# ME433_PCB_Schematic.net
KiCad netlist of a schematic drawn in EAGLE
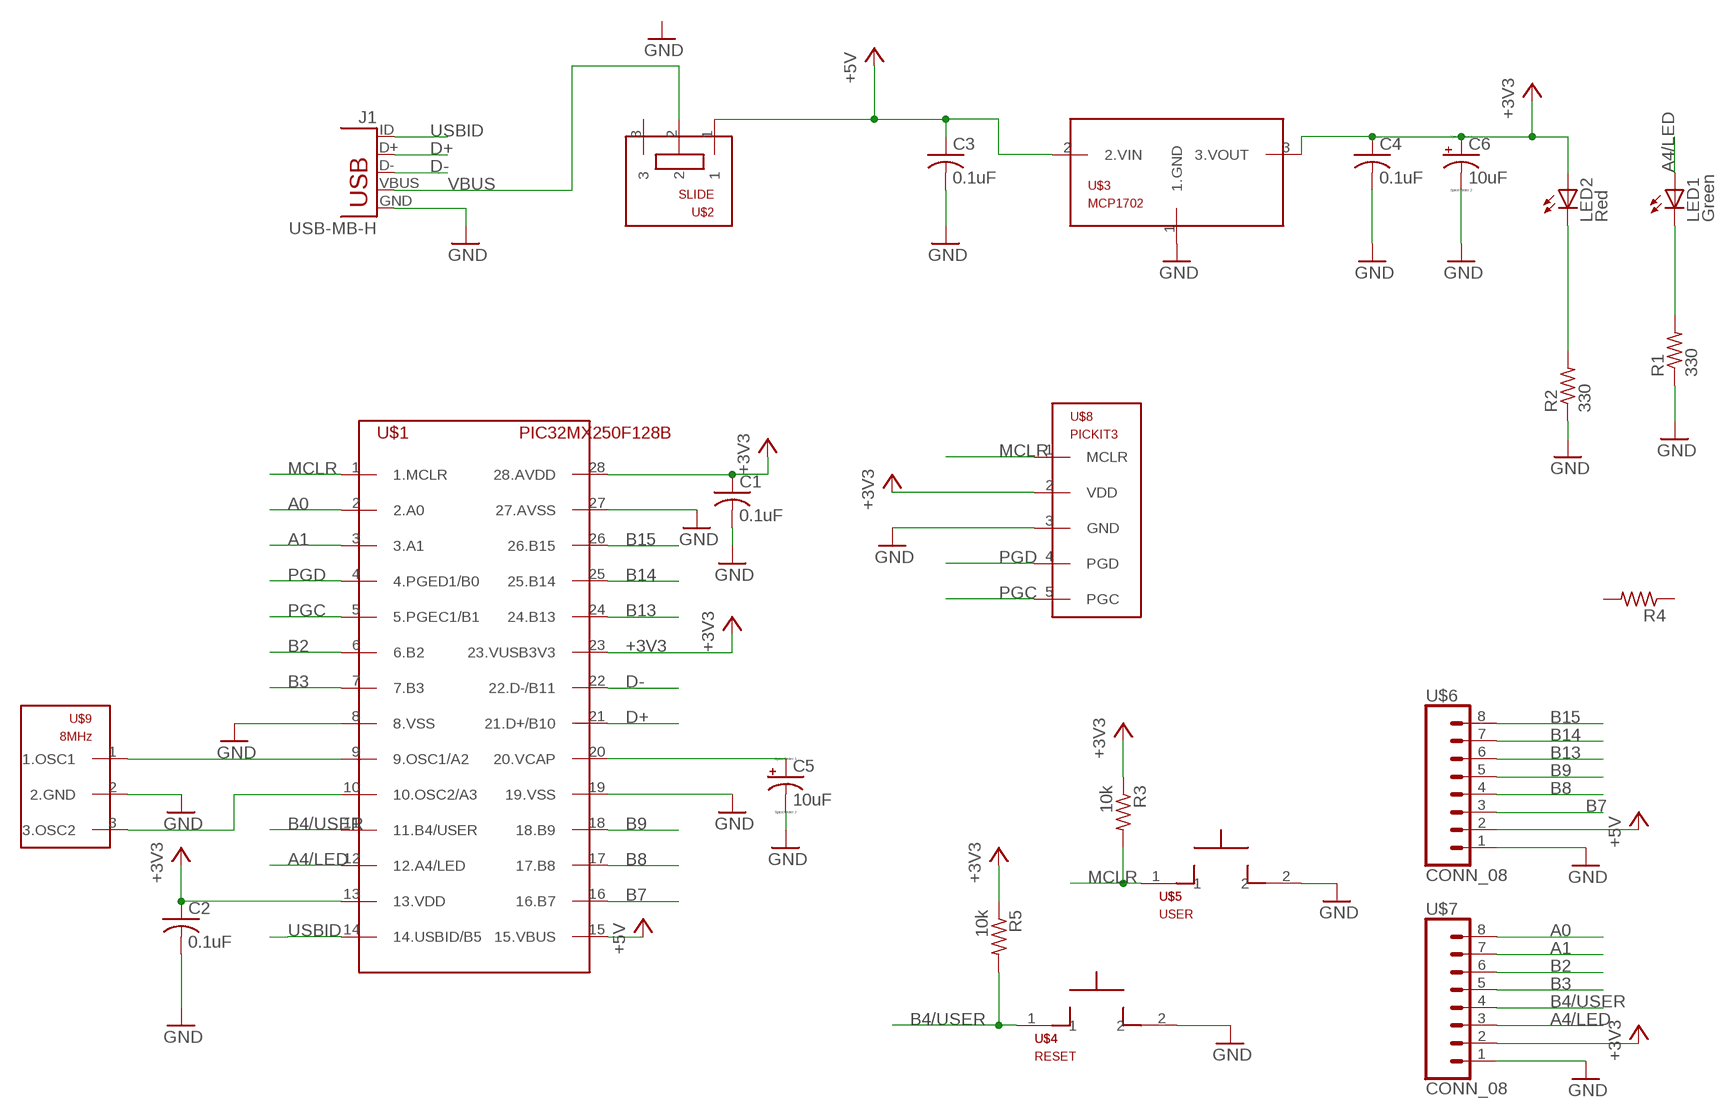
[diagram p0: schematic, sheet 1]

(export (version "E")
  (design (tool "Eeschema 10.0.6"))
  (components
    (comp (ref "C1")
      (value "0.1uF")
      (footprint "eagle-import:C025-025X050")
      (libsource (lib "eagle-import") (part "C-US025-025X050"))
    )
    (comp (ref "C2")
      (value "0.1uF")
      (footprint "eagle-import:C025-025X050")
      (libsource (lib "eagle-import") (part "C-US025-025X050"))
    )
    (comp (ref "C3")
      (value "0.1uF")
      (footprint "eagle-import:C025-025X050")
      (libsource (lib "eagle-import") (part "C-US025-025X050"))
    )
    (comp (ref "C4")
      (value "0.1uF")
      (footprint "eagle-import:C025-025X050")
      (libsource (lib "eagle-import") (part "C-US025-025X050"))
    )
    (comp (ref "C5")
      (value "10uF")
      (footprint "eagle-import:B45181B")
      (libsource (lib "eagle-import") (part "CPOL-USB45181B"))
    )
    (comp (ref "C6")
      (value "10uF")
      (footprint "eagle-import:B45181B")
      (libsource (lib "eagle-import") (part "CPOL-USB45181B"))
    )
    (comp (ref "J1")
      (value "USB-MB-H")
      (footprint "eagle-import:USB-MB-H")
      (libsource (lib "eagle-import") (part "USB-MB-H"))
    )
    (comp (ref "LED1")
      (value "Green")
      (footprint "eagle-import:LED3MM")
      (libsource (lib "eagle-import") (part "LED3MM"))
    )
    (comp (ref "LED2")
      (value "Red")
      (footprint "eagle-import:LED3MM")
      (libsource (lib "eagle-import") (part "LED3MM"))
    )
    (comp (ref "R1")
      (value "330")
      (footprint "eagle-import:0207_10")
      (libsource (lib "eagle-import") (part "R-US_0207/10"))
    )
    (comp (ref "R2")
      (value "330")
      (footprint "eagle-import:0207_10")
      (libsource (lib "eagle-import") (part "R-US_0207/10"))
    )
    (comp (ref "R3")
      (value "10k")
      (footprint "eagle-import:0207_10")
      (libsource (lib "eagle-import") (part "R-US_0207/10"))
    )
    (comp (ref "R4")
      (value "R-US_0207/10")
      (footprint "eagle-import:0207_10")
      (libsource (lib "eagle-import") (part "R-US_0207/10"))
    )
    (comp (ref "R5")
      (value "10k")
      (footprint "eagle-import:0207_10")
      (libsource (lib "eagle-import") (part "R-US_0207/10"))
    )
    (comp (ref "U$1")
      (value "PIC32MX250F128B")
      (footprint "eagle-import:DIL28-3")
      (libsource (lib "eagle-import") (part "PIC32MX250F128B"))
    )
    (comp (ref "U$2")
      (value "SLIDE")
      (footprint "eagle-import:SLIDE")
      (libsource (lib "eagle-import") (part "SLIDE"))
    )
    (comp (ref "U$3")
      (value "MCP1702")
      (footprint "eagle-import:TO92")
      (libsource (lib "eagle-import") (part "MCP1702"))
    )
    (comp (ref "U$4")
      (value "RESET")
      (footprint "eagle-import:PB")
      (libsource (lib "eagle-import") (part "PB"))
    )
    (comp (ref "U$5")
      (value "USER")
      (footprint "eagle-import:PB")
      (libsource (lib "eagle-import") (part "PB"))
    )
    (comp (ref "U$6")
      (value "CONN_08")
      (footprint "eagle-import:1X08")
      (libsource (lib "eagle-import") (part "CONN_08"))
    )
    (comp (ref "U$7")
      (value "CONN_08")
      (footprint "eagle-import:1X08")
      (libsource (lib "eagle-import") (part "CONN_08"))
    )
    (comp (ref "U$8")
      (value "PICKIT3")
      (footprint "eagle-import:1X05")
      (libsource (lib "eagle-import") (part "PICKIT3"))
    )
    (comp (ref "U$9")
      (value "8MHz")
      (footprint "eagle-import:OSC")
      (libsource (lib "eagle-import") (part "OSC"))
    )
  )
  (nets
    (net (code "1") (name "+3V3") (class "Default")
      (node (ref "C1") (pin "1") (pinfunction "1_1") (pintype "passive"))
      (node (ref "C2") (pin "1") (pinfunction "1_1") (pintype "passive"))
      (node (ref "C4") (pin "1") (pinfunction "1_1") (pintype "passive"))
      (node (ref "C6") (pin "+") (pinfunction "+_+") (pintype "passive"))
      (node (ref "LED2") (pin "A") (pinfunction "A_A") (pintype "passive"))
      (node (ref "R3") (pin "1") (pinfunction "1_1") (pintype "passive"))
      (node (ref "R5") (pin "1") (pinfunction "1_1") (pintype "passive"))
      (node (ref "U$1") (pin "13") (pinfunction "13.VDD_13") (pintype "bidirectional"))
      (node (ref "U$1") (pin "23") (pinfunction "23.VUSB3V3_23") (pintype "bidirectional"))
      (node (ref "U$1") (pin "28") (pinfunction "28.AVDD_28") (pintype "bidirectional"))
      (node (ref "U$3") (pin "3") (pinfunction "3.VOUT_3") (pintype "bidirectional"))
      (node (ref "U$7") (pin "2") (pinfunction "2_2") (pintype "passive"))
      (node (ref "U$8") (pin "2") (pinfunction "VDD_2") (pintype "bidirectional"))
    )
    (net (code "2") (name "+5V") (class "Default")
      (node (ref "C3") (pin "1") (pinfunction "1_1") (pintype "passive"))
      (node (ref "U$1") (pin "15") (pinfunction "15.VBUS_15") (pintype "bidirectional"))
      (node (ref "U$2") (pin "1") (pinfunction "1_1") (pintype "bidirectional"))
      (node (ref "U$3") (pin "2") (pinfunction "2.VIN_2") (pintype "bidirectional"))
      (node (ref "U$6") (pin "2") (pinfunction "2_2") (pintype "passive"))
    )
    (net (code "3") (name "/A0") (class "Default")
      (node (ref "U$1") (pin "2") (pinfunction "2.A0_2") (pintype "bidirectional"))
      (node (ref "U$7") (pin "8") (pinfunction "8_8") (pintype "passive"))
    )
    (net (code "4") (name "/A1") (class "Default")
      (node (ref "U$1") (pin "3") (pinfunction "3.A1_3") (pintype "bidirectional"))
      (node (ref "U$7") (pin "7") (pinfunction "7_7") (pintype "passive"))
    )
    (net (code "5") (name "/A4{slash}LED") (class "Default")
      (node (ref "LED1") (pin "A") (pinfunction "A_A") (pintype "passive"))
      (node (ref "U$1") (pin "12") (pinfunction "12.A4/LED_12") (pintype "bidirectional"))
      (node (ref "U$7") (pin "3") (pinfunction "3_3") (pintype "passive"))
    )
    (net (code "6") (name "/B2") (class "Default")
      (node (ref "U$1") (pin "6") (pinfunction "6.B2_6") (pintype "bidirectional"))
      (node (ref "U$7") (pin "6") (pinfunction "6_6") (pintype "passive"))
    )
    (net (code "7") (name "/B3") (class "Default")
      (node (ref "U$1") (pin "7") (pinfunction "7.B3_7") (pintype "bidirectional"))
      (node (ref "U$7") (pin "5") (pinfunction "5_5") (pintype "passive"))
    )
    (net (code "8") (name "/B4{slash}USER") (class "Default")
      (node (ref "R5") (pin "2") (pinfunction "2_2") (pintype "passive"))
      (node (ref "U$1") (pin "11") (pinfunction "11.B4/USER_11") (pintype "bidirectional"))
      (node (ref "U$4") (pin "1") (pinfunction "1_1") (pintype "bidirectional"))
      (node (ref "U$7") (pin "4") (pinfunction "4_4") (pintype "passive"))
    )
    (net (code "9") (name "/B7") (class "Default")
      (node (ref "U$1") (pin "16") (pinfunction "16.B7_16") (pintype "bidirectional"))
      (node (ref "U$6") (pin "3") (pinfunction "3_3") (pintype "passive"))
    )
    (net (code "10") (name "/B8") (class "Default")
      (node (ref "U$1") (pin "17") (pinfunction "17.B8_17") (pintype "bidirectional"))
      (node (ref "U$6") (pin "4") (pinfunction "4_4") (pintype "passive"))
    )
    (net (code "11") (name "/B9") (class "Default")
      (node (ref "U$1") (pin "18") (pinfunction "18.B9_18") (pintype "bidirectional"))
      (node (ref "U$6") (pin "5") (pinfunction "5_5") (pintype "passive"))
    )
    (net (code "12") (name "/B13") (class "Default")
      (node (ref "U$1") (pin "24") (pinfunction "24.B13_24") (pintype "bidirectional"))
      (node (ref "U$6") (pin "6") (pinfunction "6_6") (pintype "passive"))
    )
    (net (code "13") (name "/B14") (class "Default")
      (node (ref "U$1") (pin "25") (pinfunction "25.B14_25") (pintype "bidirectional"))
      (node (ref "U$6") (pin "7") (pinfunction "7_7") (pintype "passive"))
    )
    (net (code "14") (name "/B15") (class "Default")
      (node (ref "U$1") (pin "26") (pinfunction "26.B15_26") (pintype "bidirectional"))
      (node (ref "U$6") (pin "8") (pinfunction "8_8") (pintype "passive"))
    )
    (net (code "15") (name "/D+") (class "Default")
      (node (ref "J1") (pin "D+") (pinfunction "D+_D+") (pintype "bidirectional"))
      (node (ref "U$1") (pin "21") (pinfunction "21.D+/B10_21") (pintype "bidirectional"))
    )
    (net (code "16") (name "/D-") (class "Default")
      (node (ref "J1") (pin "D-") (pinfunction "D-_D-") (pintype "bidirectional"))
      (node (ref "U$1") (pin "22") (pinfunction "22.D-/B11_22") (pintype "bidirectional"))
    )
    (net (code "17") (name "/MCLR") (class "Default")
      (node (ref "R3") (pin "2") (pinfunction "2_2") (pintype "passive"))
      (node (ref "U$1") (pin "1") (pinfunction "1.MCLR_1") (pintype "bidirectional"))
      (node (ref "U$5") (pin "1") (pinfunction "1_1") (pintype "bidirectional"))
      (node (ref "U$8") (pin "1") (pinfunction "MCLR_1") (pintype "bidirectional"))
    )
    (net (code "18") (name "/PGC") (class "Default")
      (node (ref "U$1") (pin "5") (pinfunction "5.PGEC1/B1_5") (pintype "bidirectional"))
      (node (ref "U$8") (pin "5") (pinfunction "PGC_5") (pintype "bidirectional"))
    )
    (net (code "19") (name "/PGD") (class "Default")
      (node (ref "U$1") (pin "4") (pinfunction "4.PGED1/B0_4") (pintype "bidirectional"))
      (node (ref "U$8") (pin "4") (pinfunction "PGD_4") (pintype "bidirectional"))
    )
    (net (code "20") (name "/USBID") (class "Default")
      (node (ref "J1") (pin "ID") (pinfunction "ID_ID") (pintype "bidirectional"))
      (node (ref "U$1") (pin "14") (pinfunction "14.USBID/B5_14") (pintype "bidirectional"))
    )
    (net (code "21") (name "/VBUS") (class "Default")
      (node (ref "J1") (pin "VBUS") (pinfunction "VBUS_VBUS") (pintype "bidirectional"))
      (node (ref "U$2") (pin "2") (pinfunction "2_2") (pintype "bidirectional"))
    )
    (net (code "22") (name "GND") (class "Default")
      (node (ref "C1") (pin "2") (pinfunction "2_2") (pintype "passive"))
      (node (ref "C2") (pin "2") (pinfunction "2_2") (pintype "passive"))
      (node (ref "C3") (pin "2") (pinfunction "2_2") (pintype "passive"))
      (node (ref "C4") (pin "2") (pinfunction "2_2") (pintype "passive"))
      (node (ref "C5") (pin "-") (pinfunction "-_-") (pintype "passive"))
      (node (ref "C6") (pin "-") (pinfunction "-_-") (pintype "passive"))
      (node (ref "J1") (pin "GND") (pinfunction "GND_GND") (pintype "bidirectional"))
      (node (ref "R1") (pin "1") (pinfunction "1_1") (pintype "passive"))
      (node (ref "R2") (pin "1") (pinfunction "1_1") (pintype "passive"))
      (node (ref "U$1") (pin "19") (pinfunction "19.VSS_19") (pintype "bidirectional"))
      (node (ref "U$1") (pin "27") (pinfunction "27.AVSS_27") (pintype "bidirectional"))
      (node (ref "U$1") (pin "8") (pinfunction "8.VSS_8") (pintype "bidirectional"))
      (node (ref "U$3") (pin "1") (pinfunction "1.GND_1") (pintype "bidirectional"))
      (node (ref "U$4") (pin "2") (pinfunction "2_2") (pintype "bidirectional"))
      (node (ref "U$5") (pin "2") (pinfunction "2_2") (pintype "bidirectional"))
      (node (ref "U$6") (pin "1") (pinfunction "1_1") (pintype "passive"))
      (node (ref "U$7") (pin "1") (pinfunction "1_1") (pintype "passive"))
      (node (ref "U$8") (pin "3") (pinfunction "GND_3") (pintype "bidirectional"))
      (node (ref "U$9") (pin "2") (pinfunction "2.GND_2") (pintype "bidirectional"))
    )
    (net (code "23") (name "Net-(LED1-C)") (class "Default")
      (node (ref "LED1") (pin "K") (pinfunction "C_K") (pintype "passive"))
      (node (ref "R1") (pin "2") (pinfunction "2_2") (pintype "passive"))
    )
    (net (code "24") (name "Net-(LED2-C)") (class "Default")
      (node (ref "LED2") (pin "K") (pinfunction "C_K") (pintype "passive"))
      (node (ref "R2") (pin "2") (pinfunction "2_2") (pintype "passive"))
    )
    (net (code "25") (name "Net-(U$1-9.OSC1{slash}A2)") (class "Default")
      (node (ref "U$1") (pin "9") (pinfunction "9.OSC1/A2_9") (pintype "bidirectional"))
      (node (ref "U$9") (pin "1") (pinfunction "1.OSC1_1") (pintype "bidirectional"))
    )
    (net (code "26") (name "Net-(U$1-10.OSC2{slash}A3)") (class "Default")
      (node (ref "U$1") (pin "10") (pinfunction "10.OSC2/A3_10") (pintype "bidirectional"))
      (node (ref "U$9") (pin "3") (pinfunction "3.OSC2_3") (pintype "bidirectional"))
    )
    (net (code "27") (name "Net-(U$1-20.VCAP)") (class "Default")
      (node (ref "C5") (pin "+") (pinfunction "+_+") (pintype "passive"))
      (node (ref "U$1") (pin "20") (pinfunction "20.VCAP_20") (pintype "bidirectional"))
    )
    (net (code "28") (name "unconnected-(R4-Pad1)") (class "Default")
      (node (ref "R4") (pin "1") (pinfunction "1_1") (pintype "passive"))
    )
    (net (code "29") (name "unconnected-(R4-Pad2)") (class "Default")
      (node (ref "R4") (pin "2") (pinfunction "2_2") (pintype "passive"))
    )
    (net (code "30") (name "unconnected-(U$2-Pad3)") (class "Default")
      (node (ref "U$2") (pin "3") (pinfunction "3_3") (pintype "bidirectional"))
    )
  )
)
